# GPIO_HDR2X10.net
KiCad netlist of a schematic drawn in Altium Designer
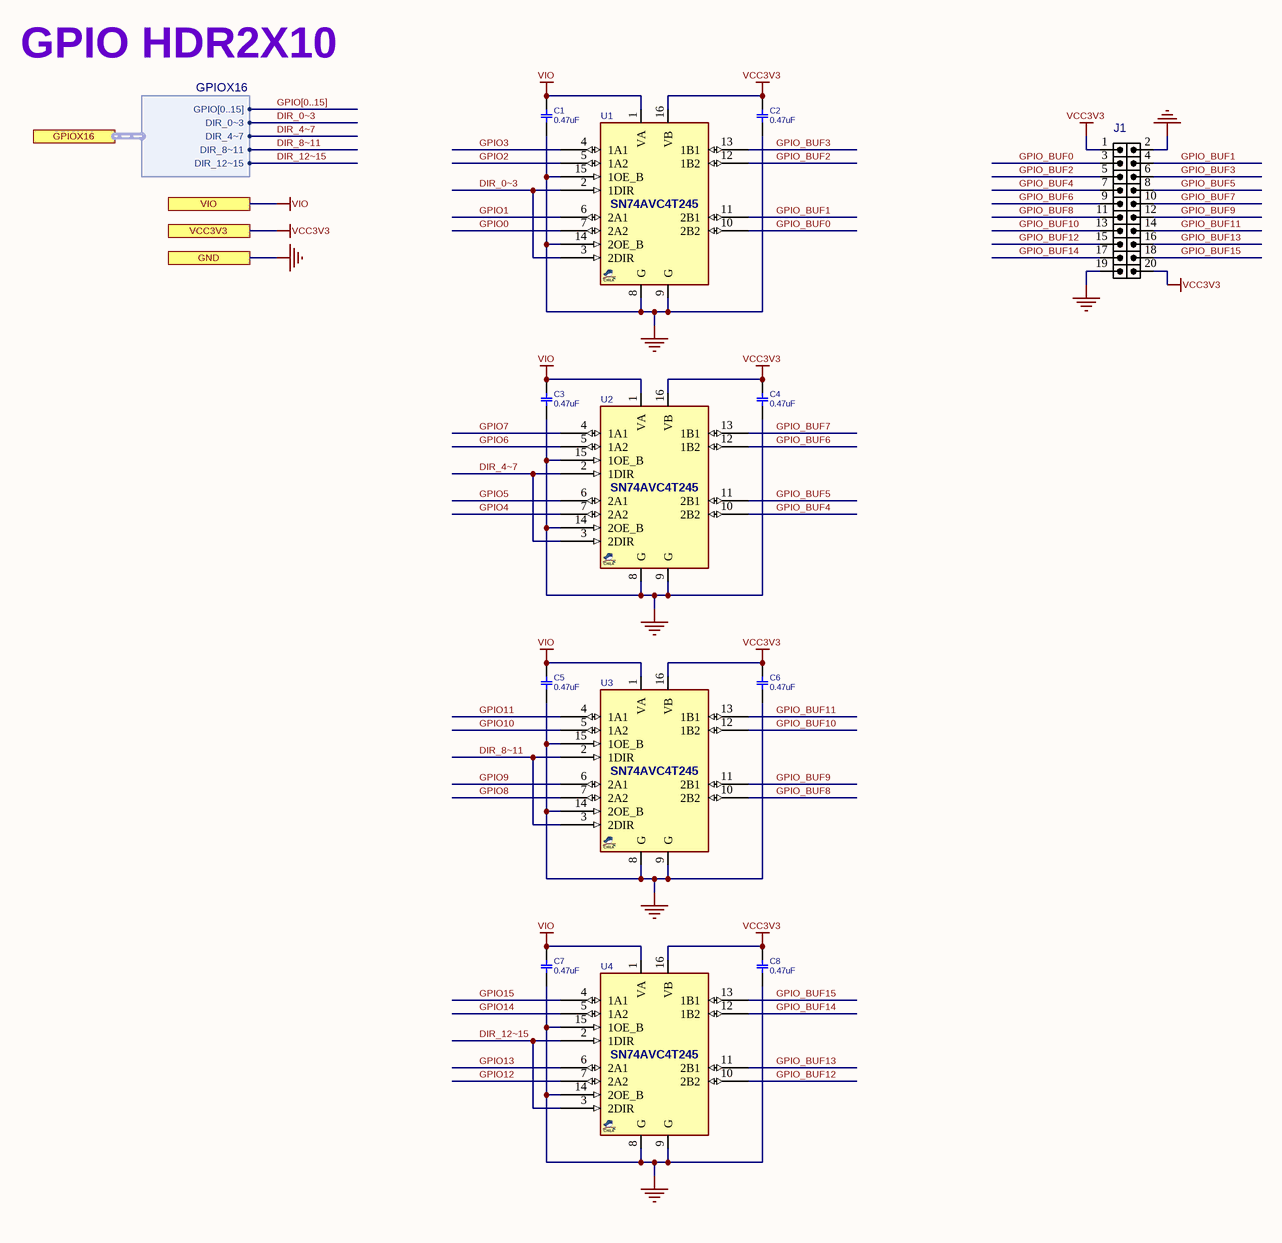
[diagram p0: GPIO_HDR2X10.SchDoc]

(export (version "E")
  (design (tool "Eeschema 10.0.6"))
  (components
    (comp (ref "C1")
      (value "0.47uF")
      (footprint "C0402")
      (description "CAP, MLCC, 100nF, 50V, X7R, 10%, 0402C")
      (fields (field (name "MANF_P#") "GCM155R71H104KE02D") (field (name "MANF") "Murata"))
      (libsource (lib "mlcc_smd_passive") (part "CAP_SMD_MLCC_100n50TDK"))
    )
    (comp (ref "C2")
      (value "0.47uF")
      (footprint "C0402")
      (description "CAP, MLCC, 100nF, 50V, X7R, 10%, 0402C")
      (fields (field (name "MANF_P#") "GCM155R71H104KE02D") (field (name "MANF") "Murata"))
      (libsource (lib "mlcc_smd_passive") (part "CAP_SMD_MLCC_100n50TDK"))
    )
    (comp (ref "C3")
      (value "0.47uF")
      (footprint "C0402")
      (description "CAP, MLCC, 100nF, 50V, X7R, 10%, 0402C")
      (fields (field (name "MANF_P#") "GCM155R71H104KE02D") (field (name "MANF") "Murata"))
      (libsource (lib "mlcc_smd_passive") (part "CAP_SMD_MLCC_100n50TDK"))
    )
    (comp (ref "C4")
      (value "0.47uF")
      (footprint "C0402")
      (description "CAP, MLCC, 100nF, 50V, X7R, 10%, 0402C")
      (fields (field (name "MANF_P#") "GCM155R71H104KE02D") (field (name "MANF") "Murata"))
      (libsource (lib "mlcc_smd_passive") (part "CAP_SMD_MLCC_100n50TDK"))
    )
    (comp (ref "C5")
      (value "0.47uF")
      (footprint "C0402")
      (description "CAP, MLCC, 100nF, 50V, X7R, 10%, 0402C")
      (fields (field (name "MANF_P#") "GCM155R71H104KE02D") (field (name "MANF") "Murata"))
      (libsource (lib "mlcc_smd_passive") (part "CAP_SMD_MLCC_100n50TDK"))
    )
    (comp (ref "C6")
      (value "0.47uF")
      (footprint "C0402")
      (description "CAP, MLCC, 100nF, 50V, X7R, 10%, 0402C")
      (fields (field (name "MANF_P#") "GCM155R71H104KE02D") (field (name "MANF") "Murata"))
      (libsource (lib "mlcc_smd_passive") (part "CAP_SMD_MLCC_100n50TDK"))
    )
    (comp (ref "C7")
      (value "0.47uF")
      (footprint "C0402")
      (description "CAP, MLCC, 100nF, 50V, X7R, 10%, 0402C")
      (fields (field (name "MANF_P#") "GCM155R71H104KE02D") (field (name "MANF") "Murata"))
      (libsource (lib "mlcc_smd_passive") (part "CAP_SMD_MLCC_100n50TDK"))
    )
    (comp (ref "C8")
      (value "0.47uF")
      (footprint "C0402")
      (description "CAP, MLCC, 100nF, 50V, X7R, 10%, 0402C")
      (fields (field (name "MANF_P#") "GCM155R71H104KE02D") (field (name "MANF") "Murata"))
      (libsource (lib "mlcc_smd_passive") (part "CAP_SMD_MLCC_100n50TDK"))
    )
    (comp (ref "J1")
      (value "HDRM_2X10")
      (footprint "IDC_2X10")
      (description "CONN, HEADER, Male, pitch: 2.54mm, 20POS")
      (libsource (lib "conn_header_2.54_st") (part "HDR_M_2X10"))
    )
    (comp (ref "U1")
      (value "SN74AVC4T245")
      (footprint "SOG65_16")
      (description "Level Translator, Quad, 3State")
      (fields (field (name "MANF") "TEXAS INSTRUMENTS") (field (name "MANF_P#") "SN74AVC4T245PWR"))
      (libsource (lib "buffer_digital") (part "SN74AVC4T245_TSSOP16"))
    )
    (comp (ref "U2")
      (value "SN74AVC4T245")
      (footprint "SOG65_16")
      (description "Level Translator, Quad, 3State")
      (fields (field (name "MANF") "TEXAS INSTRUMENTS") (field (name "MANF_P#") "SN74AVC4T245PWR"))
      (libsource (lib "buffer_digital") (part "SN74AVC4T245_TSSOP16"))
    )
    (comp (ref "U3")
      (value "SN74AVC4T245")
      (footprint "SOG65_16")
      (description "Level Translator, Quad, 3State")
      (fields (field (name "MANF") "TEXAS INSTRUMENTS") (field (name "MANF_P#") "SN74AVC4T245PWR"))
      (libsource (lib "buffer_digital") (part "SN74AVC4T245_TSSOP16"))
    )
    (comp (ref "U4")
      (value "SN74AVC4T245")
      (footprint "SOG65_16")
      (description "Level Translator, Quad, 3State")
      (fields (field (name "MANF") "TEXAS INSTRUMENTS") (field (name "MANF_P#") "SN74AVC4T245PWR"))
      (libsource (lib "buffer_digital") (part "SN74AVC4T245_TSSOP16"))
    )
  )
  (nets
    (net (code "2") (name "/DIR_0~3") (class "Default")
      (node (ref "U1") (pin "2") (pinfunction "1DIR_2") (pintype "input"))
      (node (ref "U1") (pin "3") (pinfunction "2DIR_3") (pintype "input"))
    )
    (net (code "3") (name "/DIR_4~7") (class "Default")
      (node (ref "U2") (pin "2") (pinfunction "1DIR_2") (pintype "input"))
      (node (ref "U2") (pin "3") (pinfunction "2DIR_3") (pintype "input"))
    )
    (net (code "4") (name "/DIR_8~11") (class "Default")
      (node (ref "U3") (pin "2") (pinfunction "1DIR_2") (pintype "input"))
      (node (ref "U3") (pin "3") (pinfunction "2DIR_3") (pintype "input"))
    )
    (net (code "5") (name "/DIR_12~15") (class "Default")
      (node (ref "U4") (pin "2") (pinfunction "1DIR_2") (pintype "input"))
      (node (ref "U4") (pin "3") (pinfunction "2DIR_3") (pintype "input"))
    )
    (net (code "6") (name "/GPIO0") (class "Default")
      (node (ref "U1") (pin "7") (pinfunction "2A2_7") (pintype "bidirectional"))
    )
    (net (code "7") (name "/GPIO1") (class "Default")
      (node (ref "U1") (pin "6") (pinfunction "2A1_6") (pintype "bidirectional"))
    )
    (net (code "8") (name "/GPIO2") (class "Default")
      (node (ref "U1") (pin "5") (pinfunction "1A2_5") (pintype "bidirectional"))
    )
    (net (code "9") (name "/GPIO3") (class "Default")
      (node (ref "U1") (pin "4") (pinfunction "1A1_4") (pintype "bidirectional"))
    )
    (net (code "10") (name "/GPIO4") (class "Default")
      (node (ref "U2") (pin "7") (pinfunction "2A2_7") (pintype "bidirectional"))
    )
    (net (code "11") (name "/GPIO5") (class "Default")
      (node (ref "U2") (pin "6") (pinfunction "2A1_6") (pintype "bidirectional"))
    )
    (net (code "12") (name "/GPIO6") (class "Default")
      (node (ref "U2") (pin "5") (pinfunction "1A2_5") (pintype "bidirectional"))
    )
    (net (code "13") (name "/GPIO7") (class "Default")
      (node (ref "U2") (pin "4") (pinfunction "1A1_4") (pintype "bidirectional"))
    )
    (net (code "14") (name "/GPIO8") (class "Default")
      (node (ref "U3") (pin "7") (pinfunction "2A2_7") (pintype "bidirectional"))
    )
    (net (code "15") (name "/GPIO9") (class "Default")
      (node (ref "U3") (pin "6") (pinfunction "2A1_6") (pintype "bidirectional"))
    )
    (net (code "16") (name "/GPIO10") (class "Default")
      (node (ref "U3") (pin "5") (pinfunction "1A2_5") (pintype "bidirectional"))
    )
    (net (code "17") (name "/GPIO11") (class "Default")
      (node (ref "U3") (pin "4") (pinfunction "1A1_4") (pintype "bidirectional"))
    )
    (net (code "18") (name "/GPIO12") (class "Default")
      (node (ref "U4") (pin "7") (pinfunction "2A2_7") (pintype "bidirectional"))
    )
    (net (code "19") (name "/GPIO13") (class "Default")
      (node (ref "U4") (pin "6") (pinfunction "2A1_6") (pintype "bidirectional"))
    )
    (net (code "20") (name "/GPIO14") (class "Default")
      (node (ref "U4") (pin "5") (pinfunction "1A2_5") (pintype "bidirectional"))
    )
    (net (code "21") (name "/GPIO15") (class "Default")
      (node (ref "U4") (pin "4") (pinfunction "1A1_4") (pintype "bidirectional"))
    )
    (net (code "23") (name "/GPIO_BUF0") (class "Default")
      (node (ref "J1") (pin "3") (pinfunction "3_3") (pintype "passive"))
      (node (ref "U1") (pin "10") (pinfunction "2B2_10") (pintype "bidirectional"))
    )
    (net (code "24") (name "/GPIO_BUF1") (class "Default")
      (node (ref "J1") (pin "4") (pinfunction "4_4") (pintype "passive"))
      (node (ref "U1") (pin "11") (pinfunction "2B1_11") (pintype "bidirectional"))
    )
    (net (code "25") (name "/GPIO_BUF2") (class "Default")
      (node (ref "J1") (pin "5") (pinfunction "5_5") (pintype "passive"))
      (node (ref "U1") (pin "12") (pinfunction "1B2_12") (pintype "bidirectional"))
    )
    (net (code "26") (name "/GPIO_BUF3") (class "Default")
      (node (ref "J1") (pin "6") (pinfunction "6_6") (pintype "passive"))
      (node (ref "U1") (pin "13") (pinfunction "1B1_13") (pintype "bidirectional"))
    )
    (net (code "27") (name "/GPIO_BUF4") (class "Default")
      (node (ref "J1") (pin "7") (pinfunction "7_7") (pintype "passive"))
      (node (ref "U2") (pin "10") (pinfunction "2B2_10") (pintype "bidirectional"))
    )
    (net (code "28") (name "/GPIO_BUF5") (class "Default")
      (node (ref "J1") (pin "8") (pinfunction "8_8") (pintype "passive"))
      (node (ref "U2") (pin "11") (pinfunction "2B1_11") (pintype "bidirectional"))
    )
    (net (code "29") (name "/GPIO_BUF6") (class "Default")
      (node (ref "J1") (pin "9") (pinfunction "9_9") (pintype "passive"))
      (node (ref "U2") (pin "12") (pinfunction "1B2_12") (pintype "bidirectional"))
    )
    (net (code "30") (name "/GPIO_BUF7") (class "Default")
      (node (ref "J1") (pin "10") (pinfunction "10_10") (pintype "passive"))
      (node (ref "U2") (pin "13") (pinfunction "1B1_13") (pintype "bidirectional"))
    )
    (net (code "31") (name "/GPIO_BUF8") (class "Default")
      (node (ref "J1") (pin "11") (pinfunction "11_11") (pintype "passive"))
      (node (ref "U3") (pin "10") (pinfunction "2B2_10") (pintype "bidirectional"))
    )
    (net (code "32") (name "/GPIO_BUF9") (class "Default")
      (node (ref "J1") (pin "12") (pinfunction "12_12") (pintype "passive"))
      (node (ref "U3") (pin "11") (pinfunction "2B1_11") (pintype "bidirectional"))
    )
    (net (code "33") (name "/GPIO_BUF10") (class "Default")
      (node (ref "J1") (pin "13") (pinfunction "13_13") (pintype "passive"))
      (node (ref "U3") (pin "12") (pinfunction "1B2_12") (pintype "bidirectional"))
    )
    (net (code "34") (name "/GPIO_BUF11") (class "Default")
      (node (ref "J1") (pin "14") (pinfunction "14_14") (pintype "passive"))
      (node (ref "U3") (pin "13") (pinfunction "1B1_13") (pintype "bidirectional"))
    )
    (net (code "35") (name "/GPIO_BUF12") (class "Default")
      (node (ref "J1") (pin "15") (pinfunction "15_15") (pintype "passive"))
      (node (ref "U4") (pin "10") (pinfunction "2B2_10") (pintype "bidirectional"))
    )
    (net (code "36") (name "/GPIO_BUF13") (class "Default")
      (node (ref "J1") (pin "16") (pinfunction "16_16") (pintype "passive"))
      (node (ref "U4") (pin "11") (pinfunction "2B1_11") (pintype "bidirectional"))
    )
    (net (code "37") (name "/GPIO_BUF14") (class "Default")
      (node (ref "J1") (pin "17") (pinfunction "17_17") (pintype "passive"))
      (node (ref "U4") (pin "12") (pinfunction "1B2_12") (pintype "bidirectional"))
    )
    (net (code "38") (name "/GPIO_BUF15") (class "Default")
      (node (ref "J1") (pin "18") (pinfunction "18_18") (pintype "passive"))
      (node (ref "U4") (pin "13") (pinfunction "1B1_13") (pintype "bidirectional"))
    )
    (net (code "40") (name "GND") (class "Default")
      (node (ref "C1") (pin "1") (pinfunction "1_1") (pintype "passive"))
      (node (ref "C2") (pin "1") (pinfunction "1_1") (pintype "passive"))
      (node (ref "C3") (pin "1") (pinfunction "1_1") (pintype "passive"))
      (node (ref "C4") (pin "1") (pinfunction "1_1") (pintype "passive"))
      (node (ref "C5") (pin "1") (pinfunction "1_1") (pintype "passive"))
      (node (ref "C6") (pin "1") (pinfunction "1_1") (pintype "passive"))
      (node (ref "C7") (pin "1") (pinfunction "1_1") (pintype "passive"))
      (node (ref "C8") (pin "1") (pinfunction "1_1") (pintype "passive"))
      (node (ref "J1") (pin "19") (pinfunction "19_19") (pintype "passive"))
      (node (ref "J1") (pin "2") (pinfunction "2_2") (pintype "passive"))
      (node (ref "U1") (pin "14") (pinfunction "2OE_B_14") (pintype "input"))
      (node (ref "U1") (pin "15") (pinfunction "1OE_B_15") (pintype "input"))
      (node (ref "U1") (pin "8") (pinfunction "G_8") (pintype "passive"))
      (node (ref "U1") (pin "9") (pinfunction "G_9") (pintype "passive"))
      (node (ref "U2") (pin "14") (pinfunction "2OE_B_14") (pintype "input"))
      (node (ref "U2") (pin "15") (pinfunction "1OE_B_15") (pintype "input"))
      (node (ref "U2") (pin "8") (pinfunction "G_8") (pintype "passive"))
      (node (ref "U2") (pin "9") (pinfunction "G_9") (pintype "passive"))
      (node (ref "U3") (pin "14") (pinfunction "2OE_B_14") (pintype "input"))
      (node (ref "U3") (pin "15") (pinfunction "1OE_B_15") (pintype "input"))
      (node (ref "U3") (pin "8") (pinfunction "G_8") (pintype "passive"))
      (node (ref "U3") (pin "9") (pinfunction "G_9") (pintype "passive"))
      (node (ref "U4") (pin "14") (pinfunction "2OE_B_14") (pintype "input"))
      (node (ref "U4") (pin "15") (pinfunction "1OE_B_15") (pintype "input"))
      (node (ref "U4") (pin "8") (pinfunction "G_8") (pintype "passive"))
      (node (ref "U4") (pin "9") (pinfunction "G_9") (pintype "passive"))
    )
    (net (code "41") (name "VCC3V3") (class "Default")
      (node (ref "C2") (pin "2") (pinfunction "2_2") (pintype "passive"))
      (node (ref "C4") (pin "2") (pinfunction "2_2") (pintype "passive"))
      (node (ref "C6") (pin "2") (pinfunction "2_2") (pintype "passive"))
      (node (ref "C8") (pin "2") (pinfunction "2_2") (pintype "passive"))
      (node (ref "J1") (pin "1") (pinfunction "1_1") (pintype "passive"))
      (node (ref "J1") (pin "20") (pinfunction "20_20") (pintype "passive"))
      (node (ref "U1") (pin "16") (pinfunction "VB_16") (pintype "passive"))
      (node (ref "U2") (pin "16") (pinfunction "VB_16") (pintype "passive"))
      (node (ref "U3") (pin "16") (pinfunction "VB_16") (pintype "passive"))
      (node (ref "U4") (pin "16") (pinfunction "VB_16") (pintype "passive"))
    )
    (net (code "42") (name "VIO") (class "Default")
      (node (ref "C1") (pin "2") (pinfunction "2_2") (pintype "passive"))
      (node (ref "C3") (pin "2") (pinfunction "2_2") (pintype "passive"))
      (node (ref "C5") (pin "2") (pinfunction "2_2") (pintype "passive"))
      (node (ref "C7") (pin "2") (pinfunction "2_2") (pintype "passive"))
      (node (ref "U1") (pin "1") (pinfunction "VA_1") (pintype "passive"))
      (node (ref "U2") (pin "1") (pinfunction "VA_1") (pintype "passive"))
      (node (ref "U3") (pin "1") (pinfunction "VA_1") (pintype "passive"))
      (node (ref "U4") (pin "1") (pinfunction "VA_1") (pintype "passive"))
    )
  )
)
